# queso_dip_v3.net
KiCad netlist of a schematic drawn in EAGLE
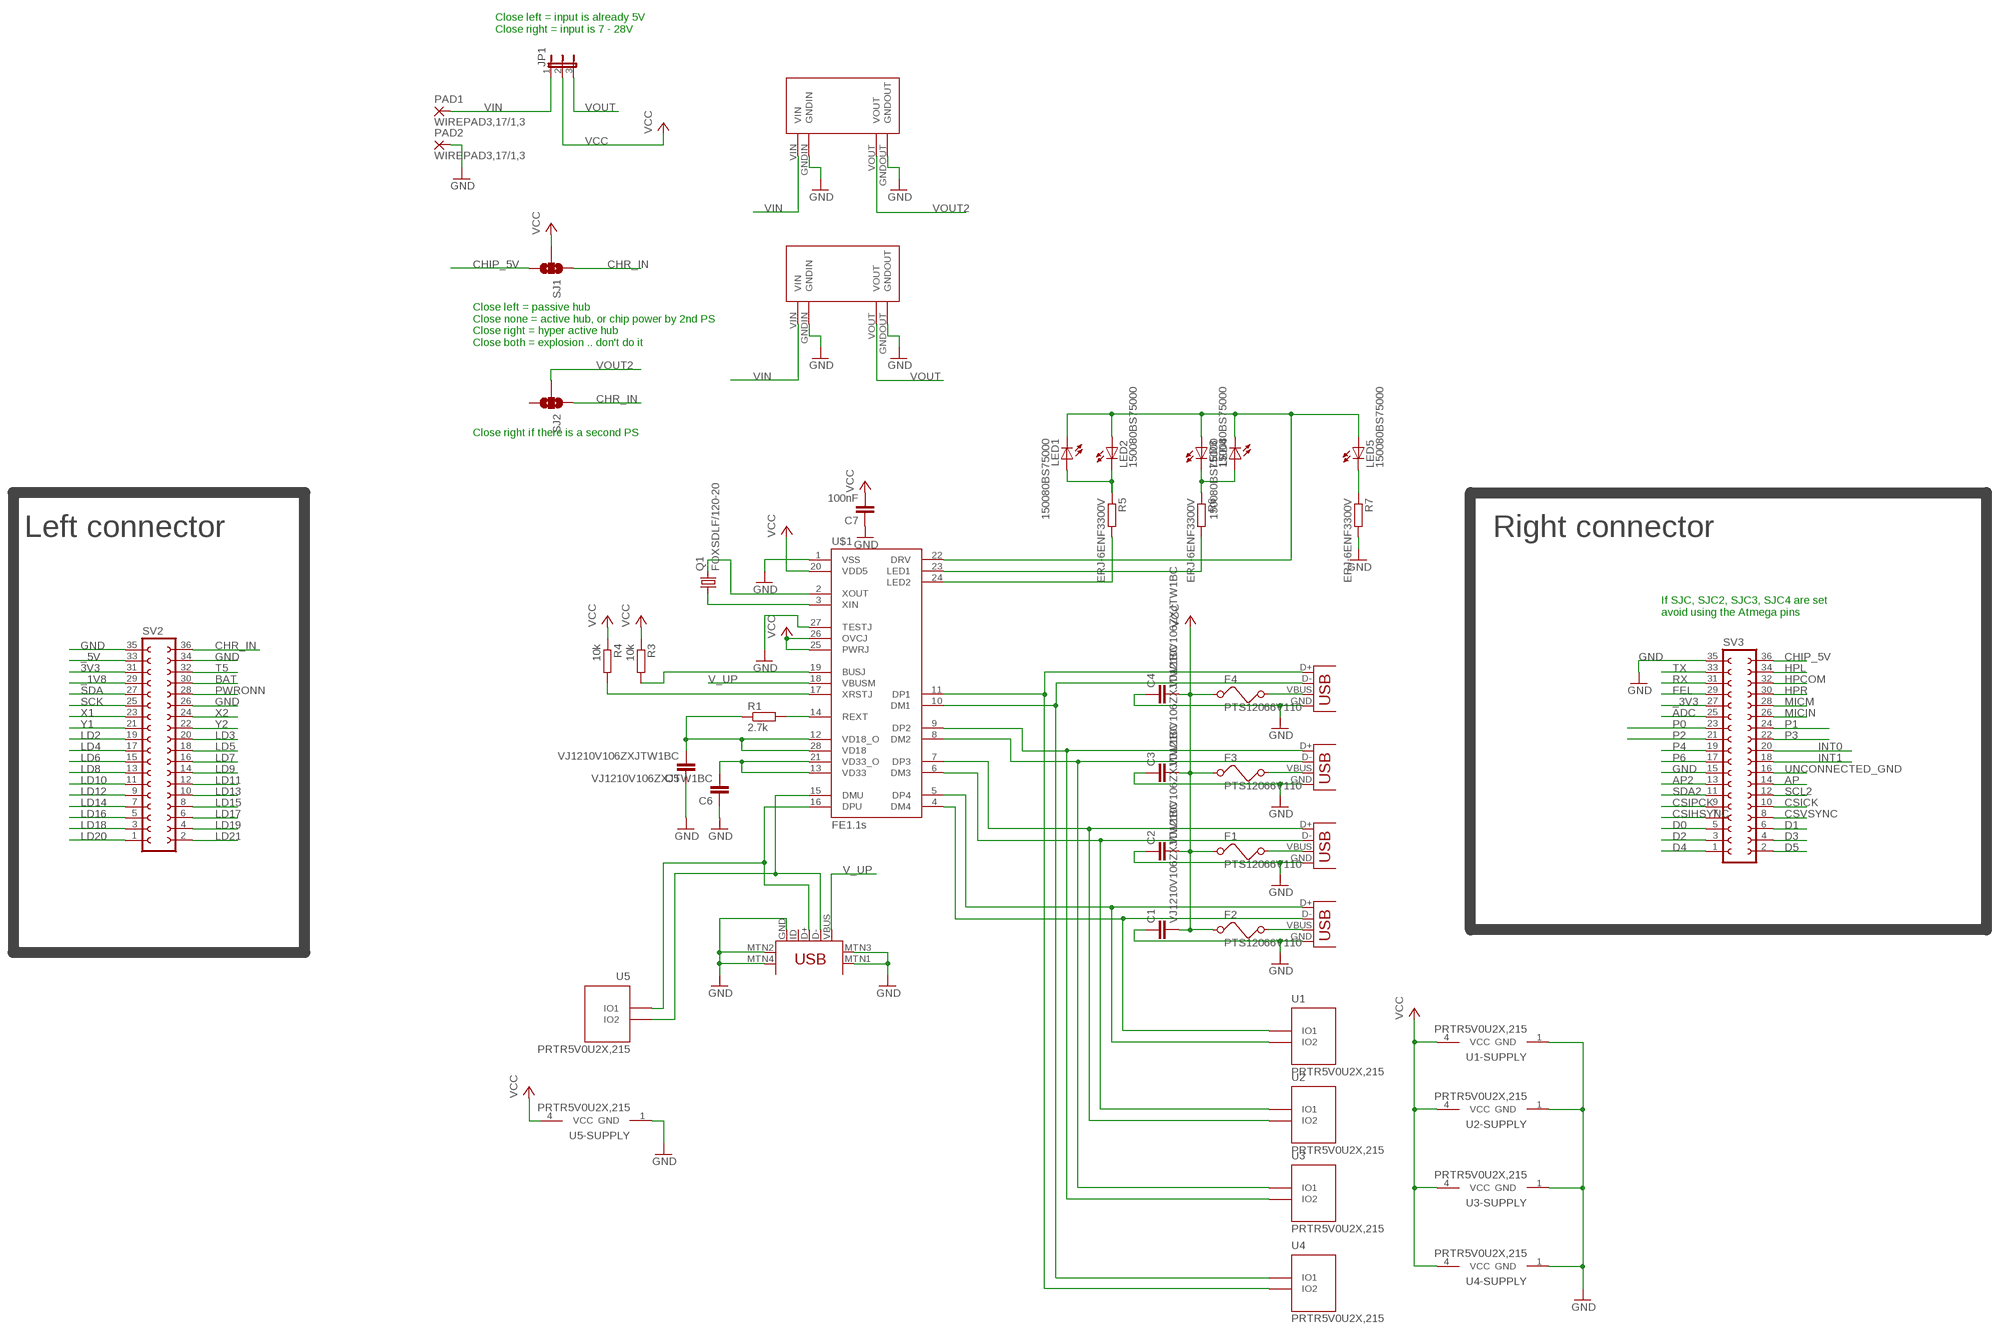
[diagram p0: schematic, sheet 1]

(export (version "E")
  (design (tool "Eeschema 10.0.6"))
  (components
    (comp (ref "C1")
      (value "VJ1210V106ZXJTW1BC")
      (footprint "eagle-import:C1210")
      (libsource (lib "eagle-import") (part "C-EUC1210"))
    )
    (comp (ref "C2")
      (value "VJ1210V106ZXJTW1BC")
      (footprint "eagle-import:C1210")
      (libsource (lib "eagle-import") (part "C-EUC1210"))
    )
    (comp (ref "C3")
      (value "VJ1210V106ZXJTW1BC")
      (footprint "eagle-import:C1210")
      (libsource (lib "eagle-import") (part "C-EUC1210"))
    )
    (comp (ref "C4")
      (value "VJ1210V106ZXJTW1BC")
      (footprint "eagle-import:C1210")
      (libsource (lib "eagle-import") (part "C-EUC1210"))
    )
    (comp (ref "C5")
      (value "VJ1210V106ZXJTW1BC")
      (footprint "eagle-import:C1210")
      (libsource (lib "eagle-import") (part "C-EUC1210"))
    )
    (comp (ref "C6")
      (value "VJ1210V106ZXJTW1BC")
      (footprint "eagle-import:C1210")
      (libsource (lib "eagle-import") (part "C-EUC1210"))
    )
    (comp (ref "C7")
      (value "100nF")
      (footprint "eagle-import:C0805")
      (libsource (lib "eagle-import") (part "C-EUC0805"))
    )
    (comp (ref "F1")
      (value "PTS12066V110")
      (footprint "eagle-import:1210")
      (libsource (lib "eagle-import") (part "FUSED"))
    )
    (comp (ref "F2")
      (value "PTS12066V110")
      (footprint "eagle-import:1210")
      (libsource (lib "eagle-import") (part "FUSED"))
    )
    (comp (ref "F3")
      (value "PTS12066V110")
      (footprint "eagle-import:1210")
      (libsource (lib "eagle-import") (part "FUSED"))
    )
    (comp (ref "F4")
      (value "PTS12066V110")
      (footprint "eagle-import:1210")
      (libsource (lib "eagle-import") (part "FUSED"))
    )
    (comp (ref "JP1")
      (value "JP2E")
      (footprint "eagle-import:JP2")
      (libsource (lib "eagle-import") (part "JP2E"))
    )
    (comp (ref "LED1")
      (value "150080BS75000")
      (footprint "eagle-import:CHIP-LED0805")
      (libsource (lib "eagle-import") (part "LEDCHIP-LED0805"))
    )
    (comp (ref "LED2")
      (value "150080BS75000")
      (footprint "eagle-import:CHIP-LED0805")
      (libsource (lib "eagle-import") (part "LEDCHIP-LED0805"))
    )
    (comp (ref "LED3")
      (value "150080BS75000")
      (footprint "eagle-import:CHIP-LED0805")
      (libsource (lib "eagle-import") (part "LEDCHIP-LED0805"))
    )
    (comp (ref "LED4")
      (value "150080BS75000")
      (footprint "eagle-import:CHIP-LED0805")
      (libsource (lib "eagle-import") (part "LEDCHIP-LED0805"))
    )
    (comp (ref "LED5")
      (value "150080BS75000")
      (footprint "eagle-import:CHIP-LED0805")
      (libsource (lib "eagle-import") (part "LEDCHIP-LED0805"))
    )
    (comp (ref "PAD1")
      (value "WIREPAD3,17/1,3")
      (footprint "eagle-import:3,17_1,3")
      (libsource (lib "eagle-import") (part "WIREPAD3,17/1,3"))
    )
    (comp (ref "PAD2")
      (value "WIREPAD3,17/1,3")
      (footprint "eagle-import:3,17_1,3")
      (libsource (lib "eagle-import") (part "WIREPAD3,17/1,3"))
    )
    (comp (ref "Q1")
      (value "FOXSDLF/120-20")
      (footprint "eagle-import:SM49")
      (libsource (lib "eagle-import") (part "CRYSTALSM49"))
    )
    (comp (ref "R1")
      (value "2.7k")
      (footprint "eagle-import:R0805")
      (libsource (lib "eagle-import") (part "R-EU_R0805"))
    )
    (comp (ref "R3")
      (value "10k")
      (footprint "eagle-import:R0805")
      (libsource (lib "eagle-import") (part "R-EU_R0805"))
    )
    (comp (ref "R4")
      (value "10k")
      (footprint "eagle-import:R0805")
      (libsource (lib "eagle-import") (part "R-EU_R0805"))
    )
    (comp (ref "R5")
      (value "ERJ-6ENF3300V")
      (footprint "eagle-import:R0805")
      (libsource (lib "eagle-import") (part "R-EU_R0805"))
    )
    (comp (ref "R6")
      (value "ERJ-6ENF3300V")
      (footprint "eagle-import:R0805")
      (libsource (lib "eagle-import") (part "R-EU_R0805"))
    )
    (comp (ref "R7")
      (value "ERJ-6ENF3300V")
      (footprint "eagle-import:R0805")
      (libsource (lib "eagle-import") (part "R-EU_R0805"))
    )
    (comp (ref "SJ1")
      (value "SOLDERJUMPER_2WAYT")
      (footprint "eagle-import:SJ_2")
      (libsource (lib "eagle-import") (part "SOLDERJUMPER_2WAYT"))
    )
    (comp (ref "SJ2")
      (value "SOLDERJUMPER_2WAYT")
      (footprint "eagle-import:SJ_2")
      (libsource (lib "eagle-import") (part "SOLDERJUMPER_2WAYT"))
    )
    (comp (ref "SV2")
      (value "FE18-2")
      (footprint "eagle-import:FE18-2")
      (libsource (lib "eagle-import") (part "FE18-2"))
    )
    (comp (ref "SV3")
      (value "FE18-2")
      (footprint "eagle-import:FE18-2")
      (libsource (lib "eagle-import") (part "FE18-2"))
    )
    (comp (ref "U$1")
      (value "FE1.1S")
      (footprint "eagle-import:FE1.1S_SSOP-28")
      (libsource (lib "eagle-import") (part "FE1.1S"))
    )
    (comp (ref "U$3")
      (value "MP1584EN")
      (footprint "eagle-import:MP1584EN")
      (libsource (lib "eagle-import") (part "MP1584EN"))
    )
    (comp (ref "U$8")
      (value "10118194-0001LF")
      (footprint "eagle-import:USB-MINIB")
      (libsource (lib "eagle-import") (part "USB-MINIB-5PIN"))
    )
    (comp (ref "U$9")
      (value "MP1584EN")
      (footprint "eagle-import:MP1584EN")
      (libsource (lib "eagle-import") (part "MP1584EN"))
    )
    (comp (ref "U1")
      (value "PRTR5V0U2X,215")
      (footprint "eagle-import:SOT-143B")
      (fields (field (name "MANUFACTURER") "NXP Semiconductors"))
      (libsource (lib "eagle-import") (part "PRTR5V0U2X?"))
    )
    (comp (ref "U2")
      (value "PRTR5V0U2X,215")
      (footprint "eagle-import:SOT-143B")
      (fields (field (name "MANUFACTURER") "NXP Semiconductors"))
      (libsource (lib "eagle-import") (part "PRTR5V0U2X?"))
    )
    (comp (ref "U3")
      (value "PRTR5V0U2X,215")
      (footprint "eagle-import:SOT-143B")
      (fields (field (name "MANUFACTURER") "NXP Semiconductors"))
      (libsource (lib "eagle-import") (part "PRTR5V0U2X?"))
    )
    (comp (ref "U4")
      (value "PRTR5V0U2X,215")
      (footprint "eagle-import:SOT-143B")
      (fields (field (name "MANUFACTURER") "NXP Semiconductors"))
      (libsource (lib "eagle-import") (part "PRTR5V0U2X?"))
    )
    (comp (ref "U5")
      (value "PRTR5V0U2X,215")
      (footprint "eagle-import:SOT-143B")
      (fields (field (name "MANUFACTURER") "NXP Semiconductors"))
      (libsource (lib "eagle-import") (part "PRTR5V0U2X?"))
    )
    (comp (ref "X1")
      (value "USB-A-HU")
      (footprint "eagle-import:USB-A-HU")
      (libsource (lib "eagle-import") (part "USB-A-HU"))
    )
    (comp (ref "X2")
      (value "USB-A-HU")
      (footprint "eagle-import:USB-A-HU")
      (libsource (lib "eagle-import") (part "USB-A-HU"))
    )
    (comp (ref "X3")
      (value "USB-A-HU")
      (footprint "eagle-import:USB-A-HU")
      (libsource (lib "eagle-import") (part "USB-A-HU"))
    )
    (comp (ref "X4")
      (value "USB-A-HU")
      (footprint "eagle-import:USB-A-HU")
      (libsource (lib "eagle-import") (part "USB-A-HU"))
    )
  )
  (nets
    (net (code "1") (name "/3V3") (class "Default")
      (node (ref "SV2") (pin "31") (pinfunction "31_31") (pintype "passive"))
    )
    (net (code "2") (name "/ADC") (class "Default")
      (node (ref "SV3") (pin "25") (pinfunction "25_25") (pintype "passive"))
    )
    (net (code "3") (name "/AP") (class "Default")
      (node (ref "SV3") (pin "14") (pinfunction "14_14") (pintype "passive"))
    )
    (net (code "4") (name "/AP2") (class "Default")
      (node (ref "SV3") (pin "13") (pinfunction "13_13") (pintype "passive"))
    )
    (net (code "5") (name "/BAT") (class "Default")
      (node (ref "SV2") (pin "30") (pinfunction "30_30") (pintype "passive"))
    )
    (net (code "6") (name "/CHIP_5V") (class "Default")
      (node (ref "SJ1") (pin "3") (pinfunction "3_3") (pintype "passive"))
      (node (ref "SV3") (pin "36") (pinfunction "36_36") (pintype "passive"))
    )
    (net (code "7") (name "/CHR_IN") (class "Default")
      (node (ref "SJ1") (pin "1") (pinfunction "1_1") (pintype "passive"))
      (node (ref "SJ2") (pin "1") (pinfunction "1_1") (pintype "passive"))
      (node (ref "SV2") (pin "36") (pinfunction "36_36") (pintype "passive"))
    )
    (net (code "8") (name "/CSICK") (class "Default")
      (node (ref "SV3") (pin "10") (pinfunction "10_10") (pintype "passive"))
    )
    (net (code "9") (name "/CSIHSYNC") (class "Default")
      (node (ref "SV3") (pin "7") (pinfunction "7_7") (pintype "passive"))
    )
    (net (code "10") (name "/CSIPCK") (class "Default")
      (node (ref "SV3") (pin "9") (pinfunction "9_9") (pintype "passive"))
    )
    (net (code "11") (name "/CSVSYNC") (class "Default")
      (node (ref "SV3") (pin "8") (pinfunction "8_8") (pintype "passive"))
    )
    (net (code "12") (name "/D0") (class "Default")
      (node (ref "SV3") (pin "5") (pinfunction "5_5") (pintype "passive"))
    )
    (net (code "13") (name "/D1") (class "Default")
      (node (ref "SV3") (pin "6") (pinfunction "6_6") (pintype "passive"))
    )
    (net (code "14") (name "/D2") (class "Default")
      (node (ref "SV3") (pin "3") (pinfunction "3_3") (pintype "passive"))
    )
    (net (code "15") (name "/D3") (class "Default")
      (node (ref "SV3") (pin "4") (pinfunction "4_4") (pintype "passive"))
    )
    (net (code "16") (name "/D4") (class "Default")
      (node (ref "SV3") (pin "1") (pinfunction "1_1") (pintype "passive"))
    )
    (net (code "17") (name "/D5") (class "Default")
      (node (ref "SV3") (pin "2") (pinfunction "2_2") (pintype "passive"))
    )
    (net (code "18") (name "/FEL") (class "Default")
      (node (ref "SV3") (pin "29") (pinfunction "29_29") (pintype "passive"))
    )
    (net (code "19") (name "/HPCOM") (class "Default")
      (node (ref "SV3") (pin "32") (pinfunction "32_32") (pintype "passive"))
    )
    (net (code "20") (name "/HPL") (class "Default")
      (node (ref "SV3") (pin "34") (pinfunction "34_34") (pintype "passive"))
    )
    (net (code "21") (name "/HPR") (class "Default")
      (node (ref "SV3") (pin "30") (pinfunction "30_30") (pintype "passive"))
    )
    (net (code "22") (name "/INT0") (class "Default")
      (node (ref "SV3") (pin "20") (pinfunction "20_20") (pintype "passive"))
    )
    (net (code "23") (name "/INT1") (class "Default")
      (node (ref "SV3") (pin "18") (pinfunction "18_18") (pintype "passive"))
    )
    (net (code "24") (name "/LD2") (class "Default")
      (node (ref "SV2") (pin "19") (pinfunction "19_19") (pintype "passive"))
    )
    (net (code "25") (name "/LD3") (class "Default")
      (node (ref "SV2") (pin "20") (pinfunction "20_20") (pintype "passive"))
    )
    (net (code "26") (name "/LD4") (class "Default")
      (node (ref "SV2") (pin "17") (pinfunction "17_17") (pintype "passive"))
    )
    (net (code "27") (name "/LD5") (class "Default")
      (node (ref "SV2") (pin "18") (pinfunction "18_18") (pintype "passive"))
    )
    (net (code "28") (name "/LD6") (class "Default")
      (node (ref "SV2") (pin "15") (pinfunction "15_15") (pintype "passive"))
    )
    (net (code "29") (name "/LD7") (class "Default")
      (node (ref "SV2") (pin "16") (pinfunction "16_16") (pintype "passive"))
    )
    (net (code "30") (name "/LD8") (class "Default")
      (node (ref "SV2") (pin "13") (pinfunction "13_13") (pintype "passive"))
    )
    (net (code "31") (name "/LD9") (class "Default")
      (node (ref "SV2") (pin "14") (pinfunction "14_14") (pintype "passive"))
    )
    (net (code "32") (name "/LD10") (class "Default")
      (node (ref "SV2") (pin "11") (pinfunction "11_11") (pintype "passive"))
    )
    (net (code "33") (name "/LD11") (class "Default")
      (node (ref "SV2") (pin "12") (pinfunction "12_12") (pintype "passive"))
    )
    (net (code "34") (name "/LD12") (class "Default")
      (node (ref "SV2") (pin "9") (pinfunction "9_9") (pintype "passive"))
    )
    (net (code "35") (name "/LD13") (class "Default")
      (node (ref "SV2") (pin "10") (pinfunction "10_10") (pintype "passive"))
    )
    (net (code "36") (name "/LD14") (class "Default")
      (node (ref "SV2") (pin "7") (pinfunction "7_7") (pintype "passive"))
    )
    (net (code "37") (name "/LD15") (class "Default")
      (node (ref "SV2") (pin "8") (pinfunction "8_8") (pintype "passive"))
    )
    (net (code "38") (name "/LD16") (class "Default")
      (node (ref "SV2") (pin "5") (pinfunction "5_5") (pintype "passive"))
    )
    (net (code "39") (name "/LD17") (class "Default")
      (node (ref "SV2") (pin "6") (pinfunction "6_6") (pintype "passive"))
    )
    (net (code "40") (name "/LD18") (class "Default")
      (node (ref "SV2") (pin "3") (pinfunction "3_3") (pintype "passive"))
    )
    (net (code "41") (name "/LD19") (class "Default")
      (node (ref "SV2") (pin "4") (pinfunction "4_4") (pintype "passive"))
    )
    (net (code "42") (name "/LD20") (class "Default")
      (node (ref "SV2") (pin "1") (pinfunction "1_1") (pintype "passive"))
    )
    (net (code "43") (name "/LD21") (class "Default")
      (node (ref "SV2") (pin "2") (pinfunction "2_2") (pintype "passive"))
    )
    (net (code "44") (name "/MICIN") (class "Default")
      (node (ref "SV3") (pin "26") (pinfunction "26_26") (pintype "passive"))
    )
    (net (code "45") (name "/MICM") (class "Default")
      (node (ref "SV3") (pin "28") (pinfunction "28_28") (pintype "passive"))
    )
    (net (code "46") (name "/P0") (class "Default")
      (node (ref "SV3") (pin "23") (pinfunction "23_23") (pintype "passive"))
    )
    (net (code "47") (name "/P1") (class "Default")
      (node (ref "SV3") (pin "24") (pinfunction "24_24") (pintype "passive"))
    )
    (net (code "48") (name "/P2") (class "Default")
      (node (ref "SV3") (pin "21") (pinfunction "21_21") (pintype "passive"))
    )
    (net (code "49") (name "/P3") (class "Default")
      (node (ref "SV3") (pin "22") (pinfunction "22_22") (pintype "passive"))
    )
    (net (code "50") (name "/P4") (class "Default")
      (node (ref "SV3") (pin "19") (pinfunction "19_19") (pintype "passive"))
    )
    (net (code "51") (name "/P6") (class "Default")
      (node (ref "SV3") (pin "17") (pinfunction "17_17") (pintype "passive"))
    )
    (net (code "52") (name "/PWRONN") (class "Default")
      (node (ref "SV2") (pin "28") (pinfunction "28_28") (pintype "passive"))
    )
    (net (code "53") (name "/RX") (class "Default")
      (node (ref "SV3") (pin "31") (pinfunction "31_31") (pintype "passive"))
    )
    (net (code "54") (name "/SCK") (class "Default")
      (node (ref "SV2") (pin "25") (pinfunction "25_25") (pintype "passive"))
    )
    (net (code "55") (name "/SCL2") (class "Default")
      (node (ref "SV3") (pin "12") (pinfunction "12_12") (pintype "passive"))
    )
    (net (code "56") (name "/SDA") (class "Default")
      (node (ref "SV2") (pin "27") (pinfunction "27_27") (pintype "passive"))
    )
    (net (code "57") (name "/SDA2") (class "Default")
      (node (ref "SV3") (pin "11") (pinfunction "11_11") (pintype "passive"))
    )
    (net (code "58") (name "/T5") (class "Default")
      (node (ref "SV2") (pin "32") (pinfunction "32_32") (pintype "passive"))
    )
    (net (code "59") (name "/TX") (class "Default")
      (node (ref "SV3") (pin "33") (pinfunction "33_33") (pintype "passive"))
    )
    (net (code "60") (name "/UNCONNECTED_GND") (class "Default")
      (node (ref "SV3") (pin "16") (pinfunction "16_16") (pintype "passive"))
    )
    (net (code "61") (name "/VIN") (class "Default")
      (node (ref "JP1") (pin "1") (pinfunction "1_1") (pintype "passive"))
      (node (ref "PAD1") (pin "1") (pinfunction "P_1") (pintype "passive"))
      (node (ref "U$3") (pin "VIN") (pinfunction "VIN_VIN") (pintype "power_in"))
      (node (ref "U$9") (pin "VIN") (pinfunction "VIN_VIN") (pintype "power_in"))
    )
    (net (code "62") (name "/VOUT") (class "Default")
      (node (ref "JP1") (pin "3") (pinfunction "3_3") (pintype "passive"))
      (node (ref "U$9") (pin "VOUT") (pinfunction "VOUT_VOUT") (pintype "power_in"))
    )
    (net (code "63") (name "/VOUT2") (class "Default")
      (node (ref "SJ2") (pin "2") (pinfunction "2_2") (pintype "passive"))
      (node (ref "U$3") (pin "VOUT") (pinfunction "VOUT_VOUT") (pintype "power_in"))
    )
    (net (code "64") (name "/V_UP") (class "Default")
      (node (ref "U$1") (pin "18") (pinfunction "VBUSM_18") (pintype "bidirectional"))
      (node (ref "U$8") (pin "VBUS") (pinfunction "VBUS_VBUS") (pintype "bidirectional"))
    )
    (net (code "65") (name "/X1") (class "Default")
      (node (ref "SV2") (pin "23") (pinfunction "23_23") (pintype "passive"))
    )
    (net (code "66") (name "/X2") (class "Default")
      (node (ref "SV2") (pin "24") (pinfunction "24_24") (pintype "passive"))
    )
    (net (code "67") (name "/Y1") (class "Default")
      (node (ref "SV2") (pin "21") (pinfunction "21_21") (pintype "passive"))
    )
    (net (code "68") (name "/Y2") (class "Default")
      (node (ref "SV2") (pin "22") (pinfunction "22_22") (pintype "passive"))
    )
    (net (code "69") (name "/_1V8") (class "Default")
      (node (ref "SV2") (pin "29") (pinfunction "29_29") (pintype "passive"))
    )
    (net (code "70") (name "/_3V3") (class "Default")
      (node (ref "SV3") (pin "27") (pinfunction "27_27") (pintype "passive"))
    )
    (net (code "71") (name "/_5V") (class "Default")
      (node (ref "SV2") (pin "33") (pinfunction "33_33") (pintype "passive"))
    )
    (net (code "72") (name "GND") (class "Default")
      (node (ref "C1") (pin "1") (pinfunction "1_1") (pintype "passive"))
      (node (ref "C2") (pin "1") (pinfunction "1_1") (pintype "passive"))
      (node (ref "C3") (pin "1") (pinfunction "1_1") (pintype "passive"))
      (node (ref "C4") (pin "1") (pinfunction "1_1") (pintype "passive"))
      (node (ref "C5") (pin "1") (pinfunction "1_1") (pintype "passive"))
      (node (ref "C6") (pin "1") (pinfunction "1_1") (pintype "passive"))
      (node (ref "C7") (pin "1") (pinfunction "1_1") (pintype "passive"))
      (node (ref "PAD2") (pin "1") (pinfunction "P_1") (pintype "passive"))
      (node (ref "R7") (pin "2") (pinfunction "2_2") (pintype "passive"))
      (node (ref "SV2") (pin "26") (pinfunction "26_26") (pintype "passive"))
      (node (ref "SV2") (pin "34") (pinfunction "34_34") (pintype "passive"))
      (node (ref "SV2") (pin "35") (pinfunction "35_35") (pintype "passive"))
      (node (ref "SV3") (pin "15") (pinfunction "15_15") (pintype "passive"))
      (node (ref "SV3") (pin "35") (pinfunction "35_35") (pintype "passive"))
      (node (ref "U$1") (pin "1") (pinfunction "VSS_1") (pintype "bidirectional"))
      (node (ref "U$1") (pin "27") (pinfunction "TESTJ_27") (pintype "bidirectional"))
      (node (ref "U$3") (pin "GNDIN") (pinfunction "GNDIN_GNDIN") (pintype "power_in"))
      (node (ref "U$3") (pin "GNDOUT") (pinfunction "GNDOUT_GNDOUT") (pintype "power_in"))
      (node (ref "U$8") (pin "GND") (pinfunction "GND_GND") (pintype "bidirectional"))
      (node (ref "U$8") (pin "MTN1") (pinfunction "MTN2_MTN1") (pintype "bidirectional"))
      (node (ref "U$8") (pin "MTN2") (pinfunction "MTN3_MTN2") (pintype "bidirectional"))
      (node (ref "U$8") (pin "MTN3") (pinfunction "MTN1_MTN3") (pintype "bidirectional"))
      (node (ref "U$8") (pin "MTN4") (pinfunction "MTN4_MTN4") (pintype "bidirectional"))
      (node (ref "U$9") (pin "GNDIN") (pinfunction "GNDIN_GNDIN") (pintype "power_in"))
      (node (ref "U$9") (pin "GNDOUT") (pinfunction "GNDOUT_GNDOUT") (pintype "power_in"))
      (node (ref "U1") (pin "1") (pinfunction "GND_1") (pintype "bidirectional"))
      (node (ref "U2") (pin "1") (pinfunction "GND_1") (pintype "bidirectional"))
      (node (ref "U3") (pin "1") (pinfunction "GND_1") (pintype "bidirectional"))
      (node (ref "U4") (pin "1") (pinfunction "GND_1") (pintype "bidirectional"))
      (node (ref "U5") (pin "1") (pinfunction "GND_1") (pintype "bidirectional"))
      (node (ref "X1") (pin "GND") (pinfunction "GND_GND") (pintype "bidirectional"))
      (node (ref "X2") (pin "GND") (pinfunction "GND_GND") (pintype "bidirectional"))
      (node (ref "X3") (pin "GND") (pinfunction "GND_GND") (pintype "bidirectional"))
      (node (ref "X4") (pin "GND") (pinfunction "GND_GND") (pintype "bidirectional"))
    )
    (net (code "73") (name "Net-(F1-Pad2)") (class "Default")
      (node (ref "F1") (pin "2") (pinfunction "2_2") (pintype "passive"))
      (node (ref "X2") (pin "VBUS") (pinfunction "VBUS_VBUS") (pintype "bidirectional"))
    )
    (net (code "74") (name "Net-(F2-Pad2)") (class "Default")
      (node (ref "F2") (pin "2") (pinfunction "2_2") (pintype "passive"))
      (node (ref "X1") (pin "VBUS") (pinfunction "VBUS_VBUS") (pintype "bidirectional"))
    )
    (net (code "75") (name "Net-(F3-Pad2)") (class "Default")
      (node (ref "F3") (pin "2") (pinfunction "2_2") (pintype "passive"))
      (node (ref "X3") (pin "VBUS") (pinfunction "VBUS_VBUS") (pintype "bidirectional"))
    )
    (net (code "76") (name "Net-(F4-Pad2)") (class "Default")
      (node (ref "F4") (pin "2") (pinfunction "2_2") (pintype "passive"))
      (node (ref "X4") (pin "VBUS") (pinfunction "VBUS_VBUS") (pintype "bidirectional"))
    )
    (net (code "77") (name "Net-(LED1-PadA)") (class "Default")
      (node (ref "LED1") (pin "A") (pinfunction "A_A") (pintype "passive"))
      (node (ref "LED2") (pin "C") (pinfunction "C_C") (pintype "passive"))
      (node (ref "R5") (pin "1") (pinfunction "1_1") (pintype "passive"))
    )
    (net (code "78") (name "Net-(LED3-PadC)") (class "Default")
      (node (ref "LED3") (pin "C") (pinfunction "C_C") (pintype "passive"))
      (node (ref "LED4") (pin "A") (pinfunction "A_A") (pintype "passive"))
      (node (ref "R6") (pin "1") (pinfunction "1_1") (pintype "passive"))
    )
    (net (code "79") (name "Net-(LED5-PadC)") (class "Default")
      (node (ref "LED5") (pin "C") (pinfunction "C_C") (pintype "passive"))
      (node (ref "R7") (pin "1") (pinfunction "1_1") (pintype "passive"))
    )
    (net (code "80") (name "Net-(U$1-BUSJ)") (class "Default")
      (node (ref "R3") (pin "2") (pinfunction "2_2") (pintype "passive"))
      (node (ref "U$1") (pin "19") (pinfunction "BUSJ_19") (pintype "bidirectional"))
    )
    (net (code "81") (name "Net-(U$1-DM1)") (class "Default")
      (node (ref "U$1") (pin "10") (pinfunction "DM1_10") (pintype "bidirectional"))
      (node (ref "U4") (pin "2") (pinfunction "IO1_2") (pintype "bidirectional"))
      (node (ref "X4") (pin "D-") (pinfunction "D-_D-") (pintype "bidirectional"))
    )
    (net (code "82") (name "Net-(U$1-DM2)") (class "Default")
      (node (ref "U$1") (pin "8") (pinfunction "DM2_8") (pintype "bidirectional"))
      (node (ref "U3") (pin "2") (pinfunction "IO1_2") (pintype "bidirectional"))
      (node (ref "X3") (pin "D-") (pinfunction "D-_D-") (pintype "bidirectional"))
    )
    (net (code "83") (name "Net-(U$1-DM3)") (class "Default")
      (node (ref "U$1") (pin "6") (pinfunction "DM3_6") (pintype "bidirectional"))
      (node (ref "U2") (pin "2") (pinfunction "IO1_2") (pintype "bidirectional"))
      (node (ref "X2") (pin "D-") (pinfunction "D-_D-") (pintype "bidirectional"))
    )
    (net (code "84") (name "Net-(U$1-DM4)") (class "Default")
      (node (ref "U$1") (pin "4") (pinfunction "DM4_4") (pintype "bidirectional"))
      (node (ref "U1") (pin "2") (pinfunction "IO1_2") (pintype "bidirectional"))
      (node (ref "X1") (pin "D-") (pinfunction "D-_D-") (pintype "bidirectional"))
    )
    (net (code "85") (name "Net-(U$1-DMU)") (class "Default")
      (node (ref "U$1") (pin "15") (pinfunction "DMU_15") (pintype "bidirectional"))
      (node (ref "U$8") (pin "D-") (pinfunction "D-_D-") (pintype "bidirectional"))
      (node (ref "U5") (pin "3") (pinfunction "IO2_3") (pintype "bidirectional"))
    )
    (net (code "86") (name "Net-(U$1-DP1)") (class "Default")
      (node (ref "U$1") (pin "11") (pinfunction "DP1_11") (pintype "bidirectional"))
      (node (ref "U4") (pin "3") (pinfunction "IO2_3") (pintype "bidirectional"))
      (node (ref "X4") (pin "D+") (pinfunction "D+_D+") (pintype "bidirectional"))
    )
    (net (code "87") (name "Net-(U$1-DP2)") (class "Default")
      (node (ref "U$1") (pin "9") (pinfunction "DP2_9") (pintype "bidirectional"))
      (node (ref "U3") (pin "3") (pinfunction "IO2_3") (pintype "bidirectional"))
      (node (ref "X3") (pin "D+") (pinfunction "D+_D+") (pintype "bidirectional"))
    )
    (net (code "88") (name "Net-(U$1-DP3)") (class "Default")
      (node (ref "U$1") (pin "7") (pinfunction "DP3_7") (pintype "bidirectional"))
      (node (ref "U2") (pin "3") (pinfunction "IO2_3") (pintype "bidirectional"))
      (node (ref "X2") (pin "D+") (pinfunction "D+_D+") (pintype "bidirectional"))
    )
    (net (code "89") (name "Net-(U$1-DP4)") (class "Default")
      (node (ref "U$1") (pin "5") (pinfunction "DP4_5") (pintype "bidirectional"))
      (node (ref "U1") (pin "3") (pinfunction "IO2_3") (pintype "bidirectional"))
      (node (ref "X1") (pin "D+") (pinfunction "D+_D+") (pintype "bidirectional"))
    )
    (net (code "90") (name "Net-(U$1-DPU)") (class "Default")
      (node (ref "U$1") (pin "16") (pinfunction "DPU_16") (pintype "bidirectional"))
      (node (ref "U$8") (pin "D+") (pinfunction "D+_D+") (pintype "bidirectional"))
      (node (ref "U5") (pin "2") (pinfunction "IO1_2") (pintype "bidirectional"))
    )
    (net (code "91") (name "Net-(U$1-DRV)") (class "Default")
      (node (ref "LED1") (pin "C") (pinfunction "C_C") (pintype "passive"))
      (node (ref "LED2") (pin "A") (pinfunction "A_A") (pintype "passive"))
      (node (ref "LED3") (pin "A") (pinfunction "A_A") (pintype "passive"))
      (node (ref "LED4") (pin "C") (pinfunction "C_C") (pintype "passive"))
      (node (ref "LED5") (pin "A") (pinfunction "A_A") (pintype "passive"))
      (node (ref "U$1") (pin "22") (pinfunction "DRV_22") (pintype "bidirectional"))
    )
    (net (code "92") (name "Net-(U$1-LED1)") (class "Default")
      (node (ref "R6") (pin "2") (pinfunction "2_2") (pintype "passive"))
      (node (ref "U$1") (pin "23") (pinfunction "LED1_23") (pintype "bidirectional"))
    )
    (net (code "93") (name "Net-(U$1-LED2)") (class "Default")
      (node (ref "R5") (pin "2") (pinfunction "2_2") (pintype "passive"))
      (node (ref "U$1") (pin "24") (pinfunction "LED2_24") (pintype "bidirectional"))
    )
    (net (code "94") (name "Net-(U$1-REXT)") (class "Default")
      (node (ref "R1") (pin "2") (pinfunction "2_2") (pintype "passive"))
      (node (ref "U$1") (pin "14") (pinfunction "REXT_14") (pintype "bidirectional"))
    )
    (net (code "95") (name "Net-(U$1-VD18)") (class "Default")
      (node (ref "C5") (pin "2") (pinfunction "2_2") (pintype "passive"))
      (node (ref "R1") (pin "1") (pinfunction "1_1") (pintype "passive"))
      (node (ref "U$1") (pin "12") (pinfunction "VD18_O_12") (pintype "bidirectional"))
      (node (ref "U$1") (pin "28") (pinfunction "VD18_28") (pintype "bidirectional"))
    )
    (net (code "96") (name "Net-(U$1-VD33)") (class "Default")
      (node (ref "C6") (pin "2") (pinfunction "2_2") (pintype "passive"))
      (node (ref "U$1") (pin "13") (pinfunction "VD33_13") (pintype "bidirectional"))
      (node (ref "U$1") (pin "21") (pinfunction "VD33_O_21") (pintype "bidirectional"))
    )
    (net (code "97") (name "Net-(U$1-XIN)") (class "Default")
      (node (ref "Q1") (pin "1") (pinfunction "1_1") (pintype "passive"))
      (node (ref "U$1") (pin "3") (pinfunction "XIN_3") (pintype "bidirectional"))
    )
    (net (code "98") (name "Net-(U$1-XOUT)") (class "Default")
      (node (ref "Q1") (pin "2") (pinfunction "2_2") (pintype "passive"))
      (node (ref "U$1") (pin "2") (pinfunction "XOUT_2") (pintype "bidirectional"))
    )
    (net (code "99") (name "Net-(U$1-XRSTJ)") (class "Default")
      (node (ref "R4") (pin "2") (pinfunction "2_2") (pintype "passive"))
      (node (ref "U$1") (pin "17") (pinfunction "XRSTJ_17") (pintype "bidirectional"))
    )
    (net (code "100") (name "VCC") (class "Default")
      (node (ref "C1") (pin "2") (pinfunction "2_2") (pintype "passive"))
      (node (ref "C2") (pin "2") (pinfunction "2_2") (pintype "passive"))
      (node (ref "C3") (pin "2") (pinfunction "2_2") (pintype "passive"))
      (node (ref "C4") (pin "2") (pinfunction "2_2") (pintype "passive"))
      (node (ref "C7") (pin "2") (pinfunction "2_2") (pintype "passive"))
      (node (ref "F1") (pin "1") (pinfunction "1_1") (pintype "passive"))
      (node (ref "F2") (pin "1") (pinfunction "1_1") (pintype "passive"))
      (node (ref "F3") (pin "1") (pinfunction "1_1") (pintype "passive"))
      (node (ref "F4") (pin "1") (pinfunction "1_1") (pintype "passive"))
      (node (ref "JP1") (pin "2") (pinfunction "2_2") (pintype "passive"))
      (node (ref "R3") (pin "1") (pinfunction "1_1") (pintype "passive"))
      (node (ref "R4") (pin "1") (pinfunction "1_1") (pintype "passive"))
      (node (ref "SJ1") (pin "2") (pinfunction "2_2") (pintype "passive"))
      (node (ref "U$1") (pin "20") (pinfunction "VDD5_20") (pintype "bidirectional"))
      (node (ref "U$1") (pin "25") (pinfunction "PWRJ_25") (pintype "bidirectional"))
      (node (ref "U$1") (pin "26") (pinfunction "OVCJ_26") (pintype "bidirectional"))
      (node (ref "U1") (pin "4") (pinfunction "VCC_4") (pintype "bidirectional"))
      (node (ref "U2") (pin "4") (pinfunction "VCC_4") (pintype "bidirectional"))
      (node (ref "U3") (pin "4") (pinfunction "VCC_4") (pintype "bidirectional"))
      (node (ref "U4") (pin "4") (pinfunction "VCC_4") (pintype "bidirectional"))
      (node (ref "U5") (pin "4") (pinfunction "VCC_4") (pintype "bidirectional"))
    )
    (net (code "101") (name "unconnected-(SJ2-Pad3)") (class "Default")
      (node (ref "SJ2") (pin "3") (pinfunction "3_3") (pintype "passive"))
    )
    (net (code "102") (name "unconnected-(U$8-PadID)") (class "Default")
      (node (ref "U$8") (pin "ID") (pinfunction "ID_ID") (pintype "bidirectional"))
    )
  )
)
